# mediator.net
KiCad netlist of a schematic drawn in EAGLE
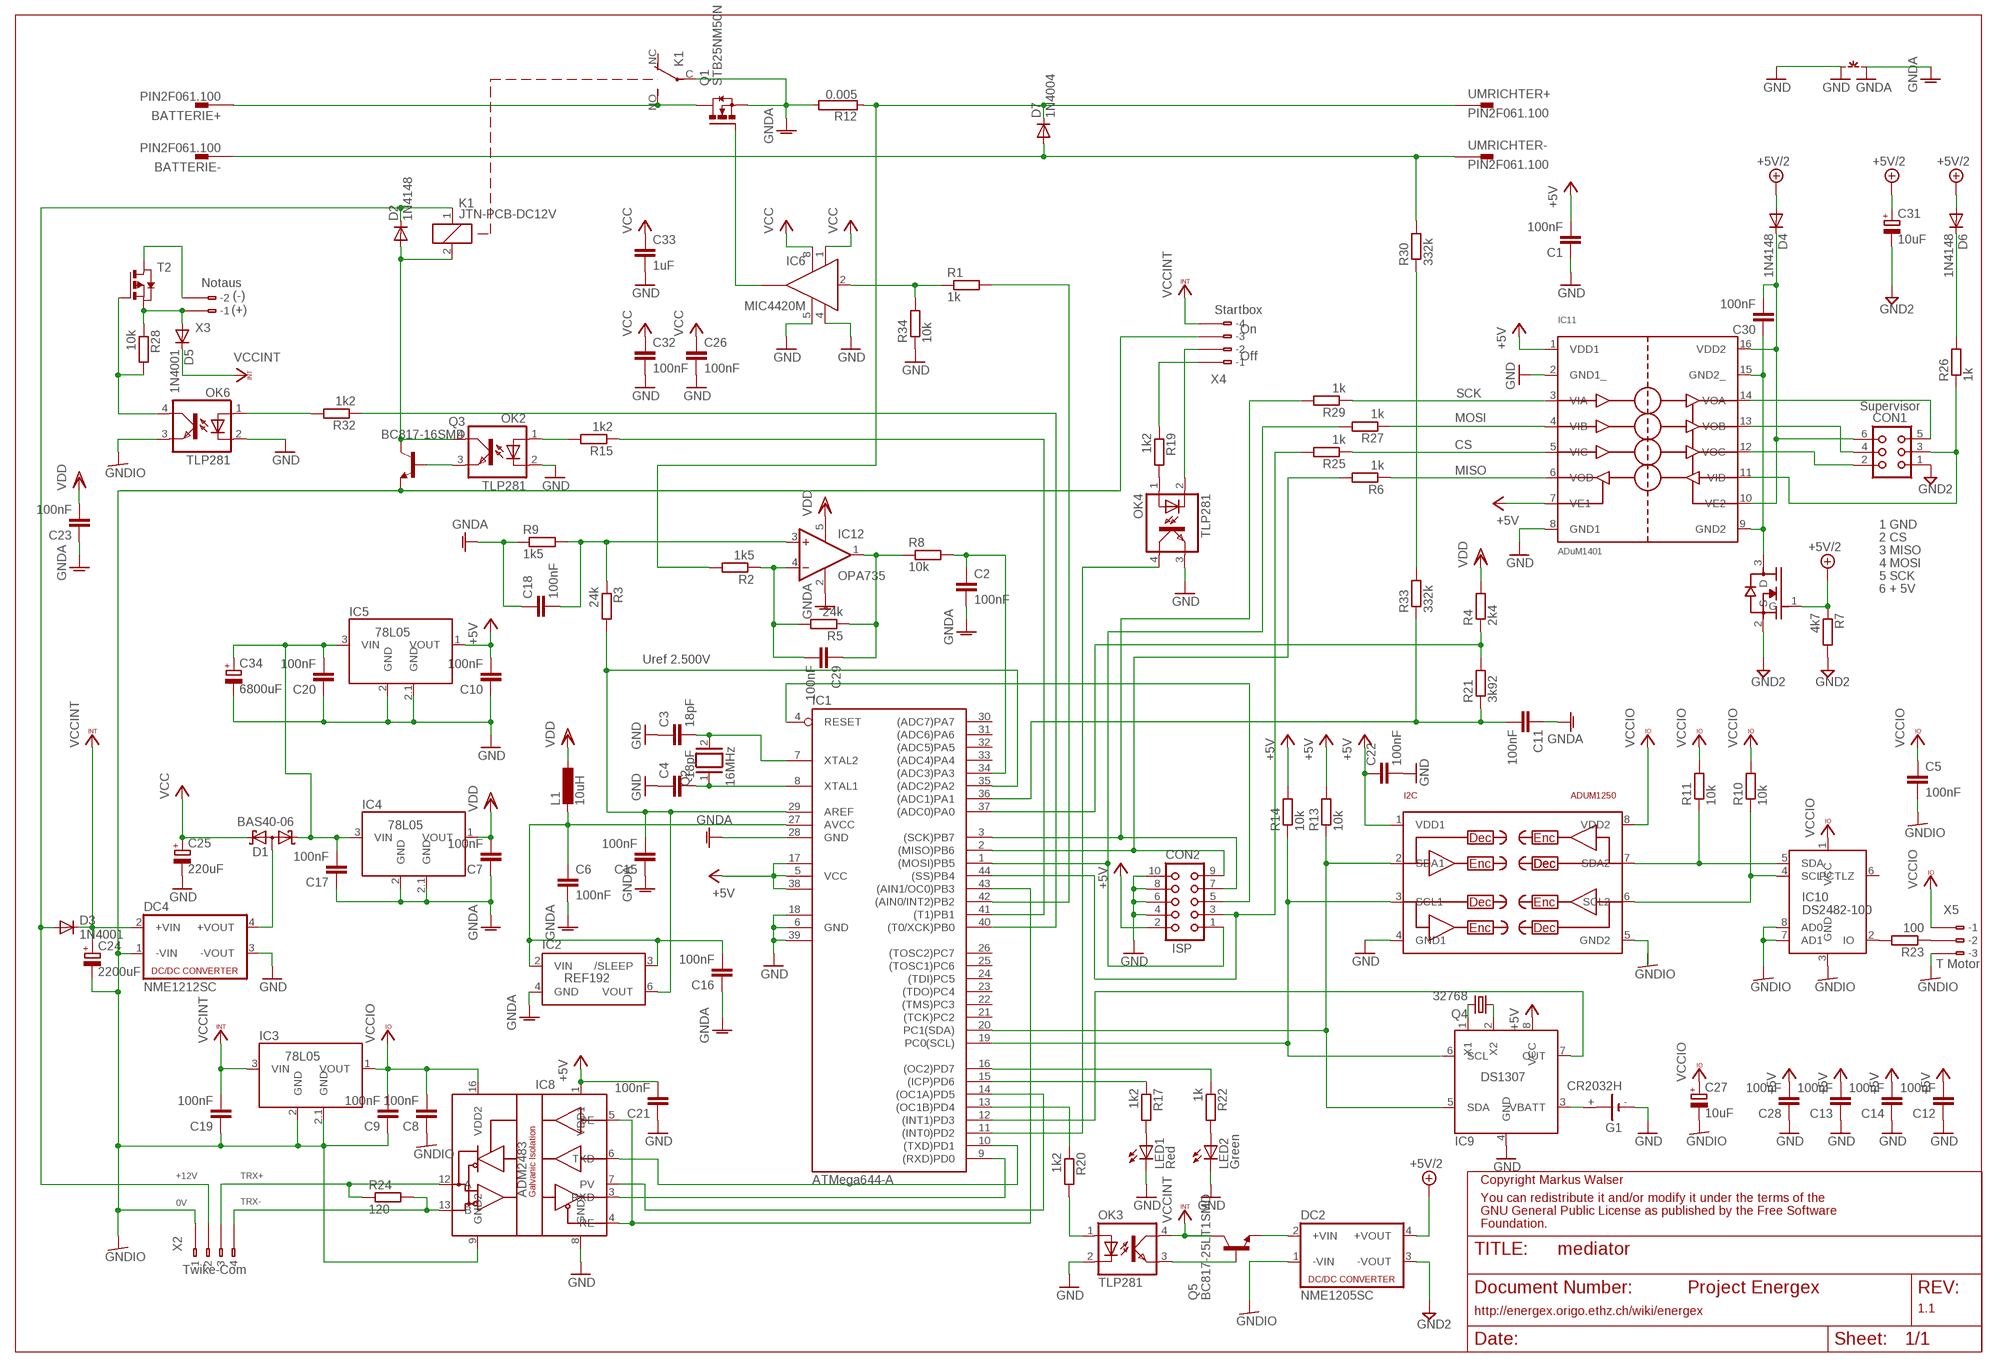
[diagram p0: schematic, sheet 1]

(export (version "E")
  (design (tool "Eeschema 10.0.6"))
  (components
    (comp (ref "BATTERIE+")
      (value "PIN2F061.100")
      (footprint "eagle-import:F061.100")
      (libsource (lib "eagle-import") (part "PIN2F061.100"))
    )
    (comp (ref "BATTERIE-")
      (value "PIN2F061.100")
      (footprint "eagle-import:F061.100")
      (libsource (lib "eagle-import") (part "PIN2F061.100"))
    )
    (comp (ref "C1")
      (value "100nF")
      (footprint "eagle-import:C0603K")
      (libsource (lib "eagle-import") (part "C-EUC0603K"))
    )
    (comp (ref "C2")
      (value "100nF")
      (footprint "eagle-import:C0603K")
      (libsource (lib "eagle-import") (part "C-EUC0603K"))
    )
    (comp (ref "C3")
      (value "18pF")
      (footprint "eagle-import:C0603K")
      (libsource (lib "eagle-import") (part "C-EUC0603K"))
    )
    (comp (ref "C4")
      (value "18pF")
      (footprint "eagle-import:C0603K")
      (libsource (lib "eagle-import") (part "C-EUC0603K"))
    )
    (comp (ref "C5")
      (value "100nF")
      (footprint "eagle-import:C0603K")
      (libsource (lib "eagle-import") (part "C-EUC0603K"))
    )
    (comp (ref "C6")
      (value "100nF")
      (footprint "eagle-import:C0603K")
      (libsource (lib "eagle-import") (part "C-EUC0603K"))
    )
    (comp (ref "C7")
      (value "100nF")
      (footprint "eagle-import:C0603K")
      (libsource (lib "eagle-import") (part "C-EUC0603K"))
    )
    (comp (ref "C8")
      (value "100nF")
      (footprint "eagle-import:C0603K")
      (libsource (lib "eagle-import") (part "C-EUC0603K"))
    )
    (comp (ref "C9")
      (value "100nF")
      (footprint "eagle-import:C0603K")
      (libsource (lib "eagle-import") (part "C-EUC0603K"))
    )
    (comp (ref "C10")
      (value "100nF")
      (footprint "eagle-import:C0603K")
      (libsource (lib "eagle-import") (part "C-EUC0603K"))
    )
    (comp (ref "C11")
      (value "100nF")
      (footprint "eagle-import:C0603K")
      (libsource (lib "eagle-import") (part "C-EUC0603K"))
    )
    (comp (ref "C12")
      (value "100nF")
      (footprint "eagle-import:C0603K")
      (libsource (lib "eagle-import") (part "C-EUC0603K"))
    )
    (comp (ref "C13")
      (value "100nF")
      (footprint "eagle-import:C0603K")
      (libsource (lib "eagle-import") (part "C-EUC0603K"))
    )
    (comp (ref "C14")
      (value "100nF")
      (footprint "eagle-import:C0603K")
      (libsource (lib "eagle-import") (part "C-EUC0603K"))
    )
    (comp (ref "C15")
      (value "100nF")
      (footprint "eagle-import:C0603K")
      (libsource (lib "eagle-import") (part "C-EUC0603K"))
    )
    (comp (ref "C16")
      (value "100nF")
      (footprint "eagle-import:C0603K")
      (libsource (lib "eagle-import") (part "C-EUC0603K"))
    )
    (comp (ref "C17")
      (value "100nF")
      (footprint "eagle-import:C0603K")
      (libsource (lib "eagle-import") (part "C-EUC0603K"))
    )
    (comp (ref "C18")
      (value "100nF")
      (footprint "eagle-import:C0603K")
      (libsource (lib "eagle-import") (part "C-EUC0603K"))
    )
    (comp (ref "C19")
      (value "100nF")
      (footprint "eagle-import:C0603K")
      (libsource (lib "eagle-import") (part "C-EUC0603K"))
    )
    (comp (ref "C20")
      (value "100nF")
      (footprint "eagle-import:C0603K")
      (libsource (lib "eagle-import") (part "C-EUC0603K"))
    )
    (comp (ref "C21")
      (value "100nF")
      (footprint "eagle-import:C0603K")
      (libsource (lib "eagle-import") (part "C-EUC0603K"))
    )
    (comp (ref "C22")
      (value "100nF")
      (footprint "eagle-import:C0603K")
      (libsource (lib "eagle-import") (part "C-EUC0603K"))
    )
    (comp (ref "C23")
      (value "100nF")
      (footprint "eagle-import:C0603K")
      (libsource (lib "eagle-import") (part "C-EUC0603K"))
    )
    (comp (ref "C24")
      (value "2200uF")
      (footprint "eagle-import:E5-10,5")
      (libsource (lib "eagle-import") (part "CPOL-EUE5-10.5"))
    )
    (comp (ref "C25")
      (value "220uF")
      (footprint "eagle-import:E2,5-6")
      (libsource (lib "eagle-import") (part "CPOL-EUE2.5-6"))
    )
    (comp (ref "C26")
      (value "100nF")
      (footprint "eagle-import:C0603K")
      (libsource (lib "eagle-import") (part "C-EUC0603K"))
    )
    (comp (ref "C27")
      (value "10uF")
      (footprint "eagle-import:SMC_A")
      (libsource (lib "eagle-import") (part "CPOL-EUSMCA"))
    )
    (comp (ref "C28")
      (value "100nF")
      (footprint "eagle-import:C0603K")
      (libsource (lib "eagle-import") (part "C-EUC0603K"))
    )
    (comp (ref "C29")
      (value "100nF")
      (footprint "eagle-import:C0603K")
      (libsource (lib "eagle-import") (part "C-EUC0603K"))
    )
    (comp (ref "C30")
      (value "100nF")
      (footprint "eagle-import:C0603K")
      (libsource (lib "eagle-import") (part "C-EUC0603K"))
    )
    (comp (ref "C31")
      (value "10uF")
      (footprint "eagle-import:SMC_A")
      (libsource (lib "eagle-import") (part "CPOL-EUSMCA"))
    )
    (comp (ref "C32")
      (value "100nF")
      (footprint "eagle-import:C0603K")
      (libsource (lib "eagle-import") (part "C-EUC0603K"))
    )
    (comp (ref "C33")
      (value "1uF")
      (footprint "eagle-import:C0603K")
      (libsource (lib "eagle-import") (part "C-EUC0603K"))
    )
    (comp (ref "C34")
      (value "6800uF")
      (footprint "eagle-import:E7,5-16")
      (libsource (lib "eagle-import") (part "CPOL-EUE7.5-16"))
    )
    (comp (ref "CON1")
      (value "CON06")
      (footprint "eagle-import:CON06")
      (libsource (lib "eagle-import") (part "CON06"))
    )
    (comp (ref "CON2")
      (value "CON10")
      (footprint "eagle-import:CON10")
      (libsource (lib "eagle-import") (part "CON10"))
    )
    (comp (ref "D1")
      (value "BAS40-06")
      (footprint "eagle-import:SOT23")
      (libsource (lib "eagle-import") (part "BAS40-06"))
    )
    (comp (ref "D2")
      (value "1N4148")
      (footprint "eagle-import:MICROMELF-R")
      (libsource (lib "eagle-import") (part "DIODE-MICROMELF-R"))
    )
    (comp (ref "D3")
      (value "1N4001")
      (footprint "eagle-import:DO214AC")
      (libsource (lib "eagle-import") (part "DIODE-DO214AC"))
    )
    (comp (ref "D4")
      (value "1N4148")
      (footprint "eagle-import:MICROMELF-R")
      (libsource (lib "eagle-import") (part "DIODE-MICROMELF-R"))
    )
    (comp (ref "D5")
      (value "1N4001")
      (footprint "eagle-import:DO214AC")
      (libsource (lib "eagle-import") (part "DIODE-DO214AC"))
    )
    (comp (ref "D6")
      (value "1N4148")
      (footprint "eagle-import:MICROMELF-R")
      (libsource (lib "eagle-import") (part "DIODE-MICROMELF-R"))
    )
    (comp (ref "D7")
      (value "1N4004")
      (footprint "eagle-import:DO41-10")
      (libsource (lib "eagle-import") (part "1N4004"))
    )
    (comp (ref "DC2")
      (value "NME1205SC")
      (footprint "eagle-import:NME")
      (fields (field (name "MF") "C & D TECHNOLOGIES, INC") (field (name "MPN") "NME1205D"))
      (libsource (lib "eagle-import") (part "NME"))
    )
    (comp (ref "DC4")
      (value "NME1212SC")
      (footprint "eagle-import:NME")
      (fields (field (name "MF") "C & D TECHNOLOGIES, INC") (field (name "MPN") "NME1205D"))
      (libsource (lib "eagle-import") (part "NME"))
    )
    (comp (ref "G1")
      (value "CR2032H")
      (footprint "eagle-import:CR2032H")
      (libsource (lib "eagle-import") (part "CR2032H"))
    )
    (comp (ref "I2C")
      (value "ADUM1250")
      (footprint "eagle-import:SO8")
      (libsource (lib "eagle-import") (part "ADUM1250"))
    )
    (comp (ref "IC1")
      (value "ATMega644-A")
      (footprint "eagle-import:TQFP44")
      (fields (field (name "MPN") "ATMEGA32-16AU"))
      (libsource (lib "eagle-import") (part "MEGA32-A"))
    )
    (comp (ref "IC2")
      (value "REF192")
      (footprint "eagle-import:SO08")
      (libsource (lib "eagle-import") (part "REF192"))
    )
    (comp (ref "IC3")
      (value "78L05")
      (footprint "eagle-import:SOT89")
      (libsource (lib "eagle-import") (part "78L05"))
    )
    (comp (ref "IC4")
      (value "78L05")
      (footprint "eagle-import:SOT89")
      (libsource (lib "eagle-import") (part "78L05"))
    )
    (comp (ref "IC5")
      (value "78L05")
      (footprint "eagle-import:SOT89")
      (libsource (lib "eagle-import") (part "78L05"))
    )
    (comp (ref "IC6")
      (value "MIC4420M")
      (footprint "eagle-import:SO-08")
      (libsource (lib "eagle-import") (part "MIC4420M"))
    )
    (comp (ref "IC8")
      (value "ADM2483")
      (footprint "eagle-import:SO16W")
      (libsource (lib "eagle-import") (part "ADM2483"))
    )
    (comp (ref "IC9")
      (value "DS1307")
      (footprint "eagle-import:SO08")
      (libsource (lib "eagle-import") (part "DS1307"))
    )
    (comp (ref "IC10")
      (value "DS2482-100")
      (footprint "eagle-import:SO08")
      (libsource (lib "eagle-import") (part "DS2482-100"))
    )
    (comp (ref "IC11")
      (value "ADuM1401")
      (footprint "eagle-import:SO16W")
      (libsource (lib "eagle-import") (part "ADUM1401"))
    )
    (comp (ref "IC12")
      (value "OPA735")
      (footprint "eagle-import:SOT23-5")
      (libsource (lib "eagle-import") (part "OPA743"))
    )
    (comp (ref "K1")
      (value "JTN-PCB-DC12V")
      (footprint "eagle-import:JT-PCB")
      (libsource (lib "eagle-import") (part "JT?-N-PCBDC12V"))
    )
    (comp (ref "L1")
      (value "10uH")
      (footprint "eagle-import:L3225M")
      (libsource (lib "eagle-import") (part "L-EUL3225M"))
    )
    (comp (ref "LED1")
      (value "Red")
      (footprint "eagle-import:CHIPLED_0805")
      (libsource (lib "eagle-import") (part "LEDCHIPLED_0805"))
    )
    (comp (ref "LED2")
      (value "Green")
      (footprint "eagle-import:CHIPLED_0805")
      (libsource (lib "eagle-import") (part "LEDCHIPLED_0805"))
    )
    (comp (ref "OK2")
      (value "TLP281")
      (footprint "eagle-import:MINI-FLAT-4")
      (libsource (lib "eagle-import") (part "TLP283"))
    )
    (comp (ref "OK3")
      (value "TLP281")
      (footprint "eagle-import:MINI-FLAT-4")
      (libsource (lib "eagle-import") (part "TLP283"))
    )
    (comp (ref "OK4")
      (value "TLP281")
      (footprint "eagle-import:MINI-FLAT-4")
      (libsource (lib "eagle-import") (part "TLP283"))
    )
    (comp (ref "OK6")
      (value "TLP281")
      (footprint "eagle-import:MINI-FLAT-4")
      (libsource (lib "eagle-import") (part "TLP283"))
    )
    (comp (ref "Q1")
      (value "STB25NM50N")
      (footprint "eagle-import:D2PACK")
      (libsource (lib "eagle-import") (part "IRF3704S"))
    )
    (comp (ref "Q2")
      (value "16MHz")
      (footprint "eagle-import:QS")
      (libsource (lib "eagle-import") (part "XTAL/S"))
    )
    (comp (ref "Q3")
      (value "BC817-16SMD")
      (footprint "eagle-import:SOT23-BEC")
      (libsource (lib "eagle-import") (part "BC817SMD-16"))
    )
    (comp (ref "Q4")
      (value "32768")
      (footprint "eagle-import:TC26H")
      (libsource (lib "eagle-import") (part "CRYSTALTC26H"))
    )
    (comp (ref "Q5")
      (value "BC817-25LT1SMD")
      (footprint "eagle-import:SOT23-BEC")
      (libsource (lib "eagle-import") (part "BC817SMD-25LT1"))
    )
    (comp (ref "R1")
      (value "1k")
      (footprint "eagle-import:R0603")
      (libsource (lib "eagle-import") (part "R-EU_R0603"))
    )
    (comp (ref "R2")
      (value "1k5")
      (footprint "eagle-import:M0805")
      (libsource (lib "eagle-import") (part "R-EU_M0805"))
    )
    (comp (ref "R3")
      (value "24k")
      (footprint "eagle-import:M0805")
      (libsource (lib "eagle-import") (part "R-EU_M0805"))
    )
    (comp (ref "R4")
      (value "2k4")
      (footprint "eagle-import:M0805")
      (libsource (lib "eagle-import") (part "R-EU_M0805"))
    )
    (comp (ref "R5")
      (value "24k")
      (footprint "eagle-import:M0805")
      (libsource (lib "eagle-import") (part "R-EU_M0805"))
    )
    (comp (ref "R6")
      (value "1k")
      (footprint "eagle-import:M0805")
      (libsource (lib "eagle-import") (part "R-EU_M0805"))
    )
    (comp (ref "R7")
      (value "4k7")
      (footprint "eagle-import:R0603")
      (libsource (lib "eagle-import") (part "R-EU_R0603"))
    )
    (comp (ref "R8")
      (value "10k")
      (footprint "eagle-import:M0805")
      (libsource (lib "eagle-import") (part "R-EU_M0805"))
    )
    (comp (ref "R9")
      (value "1k5")
      (footprint "eagle-import:M0805")
      (libsource (lib "eagle-import") (part "R-EU_M0805"))
    )
    (comp (ref "R10")
      (value "10k")
      (footprint "eagle-import:M0805")
      (libsource (lib "eagle-import") (part "R-EU_M0805"))
    )
    (comp (ref "R11")
      (value "10k")
      (footprint "eagle-import:M0805")
      (libsource (lib "eagle-import") (part "R-EU_M0805"))
    )
    (comp (ref "R12")
      (value "0.005")
      (footprint "eagle-import:KH208-8")
      (libsource (lib "eagle-import") (part "RKH208-8"))
    )
    (comp (ref "R13")
      (value "10k")
      (footprint "eagle-import:M0805")
      (libsource (lib "eagle-import") (part "R-EU_M0805"))
    )
    (comp (ref "R14")
      (value "10k")
      (footprint "eagle-import:M0805")
      (libsource (lib "eagle-import") (part "R-EU_M0805"))
    )
    (comp (ref "R15")
      (value "1k2")
      (footprint "eagle-import:R0603")
      (libsource (lib "eagle-import") (part "R-EU_R0603"))
    )
    (comp (ref "R17")
      (value "1k2")
      (footprint "eagle-import:R0603")
      (libsource (lib "eagle-import") (part "R-EU_R0603"))
    )
    (comp (ref "R19")
      (value "1k2")
      (footprint "eagle-import:R0603")
      (libsource (lib "eagle-import") (part "R-EU_R0603"))
    )
    (comp (ref "R20")
      (value "1k2")
      (footprint "eagle-import:R0603")
      (libsource (lib "eagle-import") (part "R-EU_R0603"))
    )
    (comp (ref "R21")
      (value "3k92")
      (footprint "eagle-import:M0805")
      (libsource (lib "eagle-import") (part "R-EU_M0805"))
    )
    (comp (ref "R22")
      (value "1k")
      (footprint "eagle-import:R0603")
      (libsource (lib "eagle-import") (part "R-EU_R0603"))
    )
    (comp (ref "R23")
      (value "100")
      (footprint "eagle-import:M0805")
      (libsource (lib "eagle-import") (part "R-EU_M0805"))
    )
    (comp (ref "R24")
      (value "120")
      (footprint "eagle-import:R0603")
      (libsource (lib "eagle-import") (part "R-EU_R0603"))
    )
    (comp (ref "R25")
      (value "1k")
      (footprint "eagle-import:M0805")
      (libsource (lib "eagle-import") (part "R-EU_M0805"))
    )
    (comp (ref "R26")
      (value "1k")
      (footprint "eagle-import:R0603")
      (libsource (lib "eagle-import") (part "R-EU_R0603"))
    )
    (comp (ref "R27")
      (value "1k")
      (footprint "eagle-import:M0805")
      (libsource (lib "eagle-import") (part "R-EU_M0805"))
    )
    (comp (ref "R28")
      (value "10k")
      (footprint "eagle-import:M0805")
      (libsource (lib "eagle-import") (part "R-EU_M0805"))
    )
    (comp (ref "R29")
      (value "1k")
      (footprint "eagle-import:M0805")
      (libsource (lib "eagle-import") (part "R-EU_M0805"))
    )
    (comp (ref "R30")
      (value "332k")
      (footprint "eagle-import:0207_10")
      (libsource (lib "eagle-import") (part "R-EU_0207/10"))
    )
    (comp (ref "R32")
      (value "1k2")
      (footprint "eagle-import:R0603")
      (libsource (lib "eagle-import") (part "R-EU_R0603"))
    )
    (comp (ref "R33")
      (value "332k")
      (footprint "eagle-import:0207_5V")
      (libsource (lib "eagle-import") (part "R-EU_0207/5V"))
    )
    (comp (ref "R34")
      (value "10k")
      (footprint "eagle-import:R0603")
      (libsource (lib "eagle-import") (part "R-EU_R0603"))
    )
    (comp (ref "T1")
      (value "FDN337N")
      (footprint "eagle-import:SOT23")
      (libsource (lib "eagle-import") (part "FDN337N"))
    )
    (comp (ref "T2")
      (value "PMOSSOT23")
      (footprint "eagle-import:SOT-23")
      (libsource (lib "eagle-import") (part "PMOSSOT23"))
    )
    (comp (ref "UMRICHTER+")
      (value "PIN2F061.100")
      (footprint "eagle-import:F061.100")
      (libsource (lib "eagle-import") (part "PIN2F061.100"))
    )
    (comp (ref "UMRICHTER-")
      (value "PIN2F061.100")
      (footprint "eagle-import:F061.100")
      (libsource (lib "eagle-import") (part "PIN2F061.100"))
    )
    (comp (ref "X2")
      (value "233-104")
      (footprint "eagle-import:233-104")
      (libsource (lib "eagle-import") (part "233-104"))
    )
    (comp (ref "X3")
      (value "233-102")
      (footprint "eagle-import:233-102")
      (libsource (lib "eagle-import") (part "233-102"))
    )
    (comp (ref "X4")
      (value "233-104")
      (footprint "eagle-import:233-104")
      (libsource (lib "eagle-import") (part "233-104"))
    )
    (comp (ref "X5")
      (value "233-203")
      (footprint "eagle-import:233-203")
      (libsource (lib "eagle-import") (part "233-203"))
    )
    (comp (ref "~NUDEV~1")
      (value "GND-GNDA")
      (footprint "eagle-import:GND-GNDA")
      (libsource (lib "eagle-import") (part "GND-GNDA"))
    )
  )
  (nets
    (net (code "1") (name "+5V") (class "Default")
      (node (ref "C1") (pin "2") (pinfunction "2_2") (pintype "passive"))
      (node (ref "C10") (pin "2") (pinfunction "2_2") (pintype "passive"))
      (node (ref "C12") (pin "2") (pinfunction "2_2") (pintype "passive"))
      (node (ref "C13") (pin "2") (pinfunction "2_2") (pintype "passive"))
      (node (ref "C14") (pin "2") (pinfunction "2_2") (pintype "passive"))
      (node (ref "C21") (pin "2") (pinfunction "2_2") (pintype "passive"))
      (node (ref "C22") (pin "1") (pinfunction "1_1") (pintype "passive"))
      (node (ref "C28") (pin "2") (pinfunction "2_2") (pintype "passive"))
      (node (ref "CON2") (pin "2") (pinfunction "2_2") (pintype "passive"))
      (node (ref "I2C") (pin "1") (pinfunction "VDD1_1") (pintype "power_in"))
      (node (ref "IC1") (pin "17") (pinfunction "VCC1_17") (pintype "power_in"))
      (node (ref "IC1") (pin "38") (pinfunction "VCC2_38") (pintype "power_in"))
      (node (ref "IC1") (pin "5") (pinfunction "VCC_5") (pintype "power_in"))
      (node (ref "IC11") (pin "1") (pinfunction "VDD1_1") (pintype "power_in"))
      (node (ref "IC11") (pin "7") (pinfunction "VE1_7") (pintype "input"))
      (node (ref "IC5") (pin "1") (pinfunction "VOUT_1") (pintype "power_in"))
      (node (ref "IC8") (pin "1") (pinfunction "VDD1_1") (pintype "power_in"))
      (node (ref "IC9") (pin "8") (pinfunction "VCC_8") (pintype "power_in"))
      (node (ref "R13") (pin "2") (pinfunction "2_2") (pintype "passive"))
      (node (ref "R14") (pin "2") (pinfunction "2_2") (pintype "passive"))
    )
    (net (code "2") (name "+5V{slash}2") (class "Default")
      (node (ref "C31") (pin "+") (pinfunction "+_+") (pintype "passive"))
      (node (ref "D4") (pin "A") (pinfunction "A_A") (pintype "passive"))
      (node (ref "D6") (pin "A") (pinfunction "A_A") (pintype "passive"))
      (node (ref "DC2") (pin "4") (pinfunction "+VOUT_4") (pintype "passive"))
      (node (ref "R7") (pin "1") (pinfunction "1_1") (pintype "passive"))
      (node (ref "T1") (pin "1") (pinfunction "G_1") (pintype "bidirectional"))
    )
    (net (code "3") (name "GND") (class "Default")
      (node (ref "C1") (pin "1") (pinfunction "1_1") (pintype "passive"))
      (node (ref "C10") (pin "1") (pinfunction "1_1") (pintype "passive"))
      (node (ref "C12") (pin "1") (pinfunction "1_1") (pintype "passive"))
      (node (ref "C13") (pin "1") (pinfunction "1_1") (pintype "passive"))
      (node (ref "C14") (pin "1") (pinfunction "1_1") (pintype "passive"))
      (node (ref "C20") (pin "1") (pinfunction "1_1") (pintype "passive"))
      (node (ref "C21") (pin "1") (pinfunction "1_1") (pintype "passive"))
      (node (ref "C22") (pin "2") (pinfunction "2_2") (pintype "passive"))
      (node (ref "C25") (pin "-") (pinfunction "-_-") (pintype "passive"))
      (node (ref "C26") (pin "2") (pinfunction "2_2") (pintype "passive"))
      (node (ref "C28") (pin "1") (pinfunction "1_1") (pintype "passive"))
      (node (ref "C3") (pin "1") (pinfunction "1_1") (pintype "passive"))
      (node (ref "C32") (pin "2") (pinfunction "2_2") (pintype "passive"))
      (node (ref "C33") (pin "2") (pinfunction "2_2") (pintype "passive"))
      (node (ref "C34") (pin "-") (pinfunction "-_-") (pintype "passive"))
      (node (ref "C4") (pin "1") (pinfunction "1_1") (pintype "passive"))
      (node (ref "CON2") (pin "10") (pinfunction "10_10") (pintype "passive"))
      (node (ref "CON2") (pin "4") (pinfunction "4_4") (pintype "passive"))
      (node (ref "CON2") (pin "6") (pinfunction "6_6") (pintype "passive"))
      (node (ref "CON2") (pin "8") (pinfunction "8_8") (pintype "passive"))
      (node (ref "DC4") (pin "3") (pinfunction "-VOUT_3") (pintype "passive"))
      (node (ref "G1") (pin "-") (pinfunction "-_-") (pintype "passive"))
      (node (ref "I2C") (pin "4") (pinfunction "GND1_4") (pintype "power_in"))
      (node (ref "IC1") (pin "18") (pinfunction "GND1_18") (pintype "power_in"))
      (node (ref "IC1") (pin "39") (pinfunction "GND2_39") (pintype "power_in"))
      (node (ref "IC1") (pin "6") (pinfunction "GND_6") (pintype "power_in"))
      (node (ref "IC11") (pin "2") (pinfunction "GND1__2") (pintype "power_in"))
      (node (ref "IC11") (pin "8") (pinfunction "GND1_8") (pintype "power_in"))
      (node (ref "IC5") (pin "2") (pinfunction "GND_2") (pintype "power_in"))
      (node (ref "IC5") (pin "2.1") (pinfunction "GND_2.1") (pintype "power_in"))
      (node (ref "IC6") (pin "4") (pinfunction "GND_4") (pintype "power_in"))
      (node (ref "IC6") (pin "5") (pinfunction "GND1_5") (pintype "power_in"))
      (node (ref "IC8") (pin "8") (pinfunction "GND1_8") (pintype "power_in"))
      (node (ref "IC9") (pin "4") (pinfunction "GND_4") (pintype "power_in"))
      (node (ref "LED1") (pin "C") (pinfunction "C_C") (pintype "passive"))
      (node (ref "LED2") (pin "C") (pinfunction "C_C") (pintype "passive"))
      (node (ref "OK2") (pin "2") (pinfunction "C_2") (pintype "passive"))
      (node (ref "OK3") (pin "2") (pinfunction "C_2") (pintype "passive"))
      (node (ref "OK4") (pin "3") (pinfunction "EMIT_3") (pintype "passive"))
      (node (ref "OK6") (pin "2") (pinfunction "C_2") (pintype "passive"))
      (node (ref "R34") (pin "1") (pinfunction "1_1") (pintype "passive"))
      (node (ref "~NUDEV~1") (pin "GND") (pinfunction "GND_GND") (pintype "power_in"))
    )
    (net (code "4") (name "GND2") (class "Default")
      (node (ref "C31") (pin "-") (pinfunction "-_-") (pintype "passive"))
      (node (ref "CON1") (pin "1") (pinfunction "1_1") (pintype "passive"))
      (node (ref "DC2") (pin "3") (pinfunction "-VOUT_3") (pintype "passive"))
      (node (ref "R7") (pin "2") (pinfunction "2_2") (pintype "passive"))
      (node (ref "T1") (pin "2") (pinfunction "S_2") (pintype "bidirectional"))
    )
    (net (code "5") (name "GNDA") (class "Default")
      (node (ref "C11") (pin "1") (pinfunction "1_1") (pintype "passive"))
      (node (ref "C15") (pin "1") (pinfunction "1_1") (pintype "passive"))
      (node (ref "C16") (pin "1") (pinfunction "1_1") (pintype "passive"))
      (node (ref "C17") (pin "1") (pinfunction "1_1") (pintype "passive"))
      (node (ref "C18") (pin "1") (pinfunction "1_1") (pintype "passive"))
      (node (ref "C2") (pin "2") (pinfunction "2_2") (pintype "passive"))
      (node (ref "C23") (pin "1") (pinfunction "1_1") (pintype "passive"))
      (node (ref "C6") (pin "2") (pinfunction "2_2") (pintype "passive"))
      (node (ref "C7") (pin "1") (pinfunction "1_1") (pintype "passive"))
      (node (ref "IC1") (pin "28") (pinfunction "GND_28") (pintype "power_in"))
      (node (ref "IC12") (pin "2") (pinfunction "V-_2") (pintype "power_in"))
      (node (ref "IC2") (pin "4") (pinfunction "GND_4") (pintype "bidirectional"))
      (node (ref "IC4") (pin "2") (pinfunction "GND_2") (pintype "power_in"))
      (node (ref "IC4") (pin "2.1") (pinfunction "GND_2.1") (pintype "power_in"))
      (node (ref "K1") (pin "C") (pinfunction "P_C") (pintype "passive"))
      (node (ref "Q1") (pin "3") (pinfunction "S_3") (pintype "passive"))
      (node (ref "R12") (pin "2") (pinfunction "2_2") (pintype "passive"))
      (node (ref "R9") (pin "1") (pinfunction "1_1") (pintype "passive"))
      (node (ref "~NUDEV~1") (pin "GNDA") (pinfunction "GNDA_GNDA") (pintype "power_in"))
    )
    (net (code "6") (name "GNDIO") (class "Default")
      (node (ref "C19") (pin "1") (pinfunction "1_1") (pintype "passive"))
      (node (ref "C24") (pin "-") (pinfunction "-_-") (pintype "passive"))
      (node (ref "C27") (pin "-") (pinfunction "-_-") (pintype "passive"))
      (node (ref "C5") (pin "2") (pinfunction "2_2") (pintype "passive"))
      (node (ref "C8") (pin "1") (pinfunction "1_1") (pintype "passive"))
      (node (ref "C9") (pin "1") (pinfunction "1_1") (pintype "passive"))
      (node (ref "DC2") (pin "1") (pinfunction "-VIN_1") (pintype "passive"))
      (node (ref "DC4") (pin "1") (pinfunction "-VIN_1") (pintype "passive"))
      (node (ref "I2C") (pin "5") (pinfunction "GND2_5") (pintype "power_in"))
      (node (ref "IC10") (pin "3") (pinfunction "GND_3") (pintype "power_in"))
      (node (ref "IC10") (pin "7") (pinfunction "AD1_7") (pintype "input"))
      (node (ref "IC10") (pin "8") (pinfunction "AD0_8") (pintype "input"))
      (node (ref "IC3") (pin "2") (pinfunction "GND_2") (pintype "power_in"))
      (node (ref "IC3") (pin "2.1") (pinfunction "GND_2.1") (pintype "power_in"))
      (node (ref "IC8") (pin "9") (pinfunction "GND2_9") (pintype "power_in"))
      (node (ref "OK6") (pin "3") (pinfunction "EMIT_3") (pintype "passive"))
      (node (ref "Q3") (pin "E") (pinfunction "E_E") (pintype "passive"))
      (node (ref "X2") (pin "B1") (pinfunction "B-1_B1") (pintype "passive"))
      (node (ref "X4") (pin "B3") (pinfunction "B-3_B3") (pintype "passive"))
      (node (ref "X5") (pin "B3") (pinfunction "B-3_B3") (pintype "passive"))
    )
    (net (code "7") (name "Net-(BATTERIE+-1)") (class "Default")
      (node (ref "BATTERIE+") (pin "A1") (pinfunction "1_A1") (pintype "passive"))
      (node (ref "K1") (pin "NO") (pinfunction "S_NO") (pintype "passive"))
      (node (ref "Q1") (pin "2") (pinfunction "D_2") (pintype "passive"))
    )
    (net (code "8") (name "Net-(BATTERIE--1)") (class "Default")
      (node (ref "BATTERIE-") (pin "A1") (pinfunction "1_A1") (pintype "passive"))
      (node (ref "D7") (pin "A") (pinfunction "A_A") (pintype "passive"))
      (node (ref "R30") (pin "2") (pinfunction "2_2") (pintype "passive"))
      (node (ref "UMRICHTER-") (pin "A1") (pinfunction "1_A1") (pintype "passive"))
    )
    (net (code "9") (name "Net-(D1-AA)") (class "Default")
      (node (ref "D1") (pin "3") (pinfunction "AA_3") (pintype "passive"))
      (node (ref "DC4") (pin "4") (pinfunction "+VOUT_4") (pintype "passive"))
    )
    (net (code "10") (name "Net-(D1-K1)") (class "Default")
      (node (ref "C17") (pin "2") (pinfunction "2_2") (pintype "passive"))
      (node (ref "C20") (pin "2") (pinfunction "2_2") (pintype "passive"))
      (node (ref "C34") (pin "+") (pinfunction "+_+") (pintype "passive"))
      (node (ref "D1") (pin "1") (pinfunction "K1_1") (pintype "passive"))
      (node (ref "IC4") (pin "3") (pinfunction "VIN_3") (pintype "power_in"))
      (node (ref "IC5") (pin "3") (pinfunction "VIN_3") (pintype "power_in"))
    )
    (net (code "11") (name "Net-(D6-PadC)") (class "Default")
      (node (ref "D6") (pin "C") (pinfunction "C_C") (pintype "passive"))
      (node (ref "R26") (pin "2") (pinfunction "2_2") (pintype "passive"))
    )
    (net (code "12") (name "Net-(DC2-+VIN)") (class "Default")
      (node (ref "DC2") (pin "2") (pinfunction "+VIN_2") (pintype "passive"))
      (node (ref "Q5") (pin "E") (pinfunction "E_E") (pintype "passive"))
    )
    (net (code "13") (name "Net-(I2C-SCL1)") (class "Default")
      (node (ref "I2C") (pin "3") (pinfunction "SCL1_3") (pintype "bidirectional"))
      (node (ref "IC1") (pin "19") (pinfunction "PC0(SCL)_19") (pintype "bidirectional"))
      (node (ref "IC9") (pin "6") (pinfunction "SCL_6") (pintype "bidirectional"))
      (node (ref "R14") (pin "1") (pinfunction "1_1") (pintype "passive"))
    )
    (net (code "14") (name "Net-(I2C-SCL2)") (class "Default")
      (node (ref "I2C") (pin "6") (pinfunction "SCL2_6") (pintype "bidirectional"))
      (node (ref "IC10") (pin "4") (pinfunction "SCL_4") (pintype "bidirectional"))
      (node (ref "R10") (pin "1") (pinfunction "1_1") (pintype "passive"))
    )
    (net (code "15") (name "Net-(I2C-SDA1)") (class "Default")
      (node (ref "I2C") (pin "2") (pinfunction "SDA1_2") (pintype "bidirectional"))
      (node (ref "IC1") (pin "20") (pinfunction "PC1(SDA)_20") (pintype "bidirectional"))
      (node (ref "IC9") (pin "5") (pinfunction "SDA_5") (pintype "bidirectional"))
      (node (ref "R13") (pin "1") (pinfunction "1_1") (pintype "passive"))
    )
    (net (code "16") (name "Net-(I2C-SDA2)") (class "Default")
      (node (ref "I2C") (pin "7") (pinfunction "SDA2_7") (pintype "bidirectional"))
      (node (ref "IC10") (pin "5") (pinfunction "SDA_5") (pintype "bidirectional"))
      (node (ref "R11") (pin "1") (pinfunction "1_1") (pintype "passive"))
    )
    (net (code "17") (name "Net-(IC1-(ADC0)PA0)") (class "Default")
      (node (ref "IC1") (pin "37") (pinfunction "(ADC0)PA0_37") (pintype "bidirectional"))
      (node (ref "R21") (pin "2") (pinfunction "2_2") (pintype "passive"))
      (node (ref "R4") (pin "1") (pinfunction "1_1") (pintype "passive"))
    )
    (net (code "18") (name "Net-(IC1-(ADC1)PA1)") (class "Default")
      (node (ref "C11") (pin "2") (pinfunction "2_2") (pintype "passive"))
      (node (ref "IC1") (pin "36") (pinfunction "(ADC1)PA1_36") (pintype "bidirectional"))
      (node (ref "R21") (pin "1") (pinfunction "1_1") (pintype "passive"))
      (node (ref "R33") (pin "1") (pinfunction "1_1") (pintype "passive"))
    )
    (net (code "19") (name "Net-(IC1-(ADC2)PA2)") (class "Default")
      (node (ref "C15") (pin "2") (pinfunction "2_2") (pintype "passive"))
      (node (ref "IC1") (pin "29") (pinfunction "AREF_29") (pintype "passive"))
      (node (ref "IC1") (pin "35") (pinfunction "(ADC2)PA2_35") (pintype "bidirectional"))
      (node (ref "IC2") (pin "6") (pinfunction "VOUT_6") (pintype "bidirectional"))
      (node (ref "R3") (pin "2") (pinfunction "2_2") (pintype "passive"))
    )
    (net (code "20") (name "Net-(IC1-(ADC3)PA3)") (class "Default")
      (node (ref "C2") (pin "1") (pinfunction "1_1") (pintype "passive"))
      (node (ref "IC1") (pin "34") (pinfunction "(ADC3)PA3_34") (pintype "bidirectional"))
      (node (ref "R8") (pin "2") (pinfunction "2_2") (pintype "passive"))
    )
    (net (code "21") (name "Net-(IC1-(AIN0{slash}INT2)PB2)") (class "Default")
      (node (ref "IC1") (pin "42") (pinfunction "(AIN0/INT2)PB2_42") (pintype "bidirectional"))
      (node (ref "R1") (pin "2") (pinfunction "2_2") (pintype "passive"))
    )
    (net (code "22") (name "Net-(IC1-(AIN1{slash}OC0)PB3)") (class "Default")
      (node (ref "IC1") (pin "43") (pinfunction "(AIN1/OC0)PB3_43") (pintype "bidirectional"))
      (node (ref "IC8") (pin "4") (pinfunction "RE_4") (pintype "input"))
      (node (ref "IC8") (pin "5") (pinfunction "DE_5") (pintype "input"))
    )
    (net (code "23") (name "Net-(IC1-(ICP)PD6)") (class "Default")
      (node (ref "IC1") (pin "15") (pinfunction "(ICP)PD6_15") (pintype "bidirectional"))
      (node (ref "R17") (pin "1") (pinfunction "1_1") (pintype "passive"))
    )
    (net (code "24") (name "Net-(IC1-(INT0)PD2)") (class "Default")
      (node (ref "IC1") (pin "11") (pinfunction "(INT0)PD2_11") (pintype "bidirectional"))
      (node (ref "OK4") (pin "4") (pinfunction "COL_4") (pintype "passive"))
    )
    (net (code "25") (name "Net-(IC1-(INT1)PD3)") (class "Default")
      (node (ref "IC1") (pin "12") (pinfunction "(INT1)PD3_12") (pintype "bidirectional"))
      (node (ref "IC9") (pin "7") (pinfunction "OUT_7") (pintype "output"))
    )
    (net (code "26") (name "Net-(IC1-(MISO)PB6)") (class "Default")
      (node (ref "CON2") (pin "9") (pinfunction "9_9") (pintype "passive"))
      (node (ref "IC1") (pin "2") (pinfunction "(MISO)PB6_2") (pintype "bidirectional"))
      (node (ref "R6") (pin "2") (pinfunction "2_2") (pintype "passive"))
    )
    (net (code "27") (name "Net-(IC1-(MOSI)PB5)") (class "Default")
      (node (ref "CON2") (pin "1") (pinfunction "1_1") (pintype "passive"))
      (node (ref "IC1") (pin "1") (pinfunction "(MOSI)PB5_1") (pintype "bidirectional"))
      (node (ref "R27") (pin "2") (pinfunction "2_2") (pintype "passive"))
    )
    (net (code "28") (name "Net-(IC1-(OC1A)PD5)") (class "Default")
      (node (ref "IC1") (pin "14") (pinfunction "(OC1A)PD5_14") (pintype "bidirectional"))
      (node (ref "IC8") (pin "7") (pinfunction "PV_7") (pintype "input"))
    )
    (net (code "29") (name "Net-(IC1-(OC1B)PD4)") (class "Default")
      (node (ref "IC1") (pin "13") (pinfunction "(OC1B)PD4_13") (pintype "bidirectional"))
      (node (ref "R20") (pin "1") (pinfunction "1_1") (pintype "passive"))
    )
    (net (code "30") (name "Net-(IC1-(OC2)PD7)") (class "Default")
      (node (ref "IC1") (pin "16") (pinfunction "(OC2)PD7_16") (pintype "bidirectional"))
      (node (ref "R22") (pin "1") (pinfunction "1_1") (pintype "passive"))
    )
    (net (code "31") (name "Net-(IC1-(RXD)PD0)") (class "Default")
      (node (ref "IC1") (pin "9") (pinfunction "(RXD)PD0_9") (pintype "bidirectional"))
      (node (ref "IC8") (pin "3") (pinfunction "RXD_3") (pintype "output"))
    )
    (net (code "32") (name "Net-(IC1-(SCK)PB7)") (class "Default")
      (node (ref "CON2") (pin "7") (pinfunction "7_7") (pintype "passive"))
      (node (ref "IC1") (pin "3") (pinfunction "(SCK)PB7_3") (pintype "bidirectional"))
      (node (ref "R29") (pin "2") (pinfunction "2_2") (pintype "passive"))
    )
    (net (code "33") (name "Net-(IC1-(SS)PB4)") (class "Default")
      (node (ref "CON2") (pin "3") (pinfunction "3_3") (pintype "passive"))
      (node (ref "IC1") (pin "44") (pinfunction "(SS)PB4_44") (pintype "bidirectional"))
      (node (ref "R25") (pin "2") (pinfunction "2_2") (pintype "passive"))
    )
    (net (code "34") (name "Net-(IC1-(T0{slash}XCK)PB0)") (class "Default")
      (node (ref "IC1") (pin "40") (pinfunction "(T0/XCK)PB0_40") (pintype "bidirectional"))
      (node (ref "R32") (pin "1") (pinfunction "1_1") (pintype "passive"))
    )
    (net (code "35") (name "Net-(IC1-(T1)PB1)") (class "Default")
      (node (ref "IC1") (pin "41") (pinfunction "(T1)PB1_41") (pintype "bidirectional"))
      (node (ref "R15") (pin "1") (pinfunction "1_1") (pintype "passive"))
    )
    (net (code "36") (name "Net-(IC1-(TXD)PD1)") (class "Default")
      (node (ref "IC1") (pin "10") (pinfunction "(TXD)PD1_10") (pintype "bidirectional"))
      (node (ref "IC8") (pin "6") (pinfunction "TXD_6") (pintype "input"))
    )
    (net (code "37") (name "Net-(IC1-AVCC)") (class "Default")
      (node (ref "C16") (pin "2") (pinfunction "2_2") (pintype "passive"))
      (node (ref "C6") (pin "1") (pinfunction "1_1") (pintype "passive"))
      (node (ref "IC1") (pin "27") (pinfunction "AVCC_27") (pintype "power_in"))
      (node (ref "IC2") (pin "2") (pinfunction "VIN_2") (pintype "bidirectional"))
      (node (ref "IC2") (pin "3") (pinfunction "/SLEEP_3") (pintype "bidirectional"))
      (node (ref "L1") (pin "2") (pinfunction "2_2") (pintype "passive"))
    )
    (net (code "38") (name "Net-(IC1-RESET)") (class "Default")
      (node (ref "CON2") (pin "5") (pinfunction "5_5") (pintype "passive"))
      (node (ref "IC1") (pin "4") (pinfunction "RESET_4") (pintype "input"))
    )
    (net (code "39") (name "Net-(IC1-XTAL1)") (class "Default")
      (node (ref "C4") (pin "2") (pinfunction "2_2") (pintype "passive"))
      (node (ref "IC1") (pin "8") (pinfunction "XTAL1_8") (pintype "bidirectional"))
      (node (ref "Q2") (pin "1") (pinfunction "1_1") (pintype "passive"))
    )
    (net (code "40") (name "Net-(IC1-XTAL2)") (class "Default")
      (node (ref "C3") (pin "2") (pinfunction "2_2") (pintype "passive"))
      (node (ref "IC1") (pin "7") (pinfunction "XTAL2_7") (pintype "bidirectional"))
      (node (ref "Q2") (pin "2") (pinfunction "2_2") (pintype "passive"))
    )
    (net (code "41") (name "Net-(IC6-IN)") (class "Default")
      (node (ref "IC6") (pin "2") (pinfunction "IN_2") (pintype "input"))
      (node (ref "R1") (pin "1") (pinfunction "1_1") (pintype "passive"))
      (node (ref "R34") (pin "2") (pinfunction "2_2") (pintype "passive"))
    )
    (net (code "42") (name "Net-(IC8-A)") (class "Default")
      (node (ref "IC8") (pin "12") (pinfunction "A_12") (pintype "bidirectional"))
      (node (ref "R24") (pin "1") (pinfunction "1_1") (pintype "passive"))
      (node (ref "X2") (pin "B3") (pinfunction "B-3_B3") (pintype "passive"))
    )
    (net (code "43") (name "Net-(IC8-B)") (class "Default")
      (node (ref "IC8") (pin "13") (pinfunction "B_13") (pintype "bidirectional"))
      (node (ref "R24") (pin "2") (pinfunction "2_2") (pintype "passive"))
      (node (ref "X2") (pin "B4") (pinfunction "B-4_B4") (pintype "passive"))
    )
    (net (code "44") (name "Net-(IC9-VBATT)") (class "Default")
      (node (ref "G1") (pin "+") (pinfunction "+_+") (pintype "passive"))
      (node (ref "IC9") (pin "3") (pinfunction "VBATT_3") (pintype "power_in"))
    )
    (net (code "45") (name "Net-(IC9-X1)") (class "Default")
      (node (ref "IC9") (pin "1") (pinfunction "X1_1") (pintype "bidirectional"))
      (node (ref "Q4") (pin "2") (pinfunction "2_2") (pintype "passive"))
    )
    (net (code "46") (name "Net-(IC9-X2)") (class "Default")
      (node (ref "IC9") (pin "2") (pinfunction "X2_2") (pintype "bidirectional"))
      (node (ref "Q4") (pin "1") (pinfunction "1_1") (pintype "passive"))
    )
    (net (code "47") (name "Net-(IC10-IO)") (class "Default")
      (node (ref "IC10") (pin "2") (pinfunction "IO_2") (pintype "bidirectional"))
      (node (ref "R23") (pin "2") (pinfunction "2_2") (pintype "passive"))
    )
    (net (code "48") (name "Net-(IC11-GND2)") (class "Default")
      (node (ref "C30") (pin "1") (pinfunction "1_1") (pintype "passive"))
      (node (ref "IC11") (pin "15") (pinfunction "GND2__15") (pintype "power_in"))
      (node (ref "IC11") (pin "9") (pinfunction "GND2_9") (pintype "power_in"))
      (node (ref "T1") (pin "3") (pinfunction "D_3") (pintype "bidirectional"))
    )
    (net (code "49") (name "Net-(IC11-VDD2)") (class "Default")
      (node (ref "C30") (pin "2") (pinfunction "2_2") (pintype "passive"))
      (node (ref "CON1") (pin "6") (pinfunction "6_6") (pintype "passive"))
      (node (ref "D4") (pin "C") (pinfunction "C_C") (pintype "passive"))
      (node (ref "IC11") (pin "10") (pinfunction "VE2_10") (pintype "input"))
      (node (ref "IC11") (pin "16") (pinfunction "VDD2_16") (pintype "power_in"))
    )
    (net (code "50") (name "Net-(IC11-VIA)") (class "Default")
      (node (ref "IC11") (pin "3") (pinfunction "VIA_3") (pintype "input"))
      (node (ref "R29") (pin "1") (pinfunction "1_1") (pintype "passive"))
    )
    (net (code "51") (name "Net-(IC11-VIB)") (class "Default")
      (node (ref "IC11") (pin "4") (pinfunction "VIB_4") (pintype "input"))
      (node (ref "R27") (pin "1") (pinfunction "1_1") (pintype "passive"))
    )
    (net (code "52") (name "Net-(IC11-VIC)") (class "Default")
      (node (ref "IC11") (pin "5") (pinfunction "VIC_5") (pintype "input"))
      (node (ref "R25") (pin "1") (pinfunction "1_1") (pintype "passive"))
    )
    (net (code "53") (name "Net-(IC11-VID)") (class "Default")
      (node (ref "CON1") (pin "3") (pinfunction "3_3") (pintype "passive"))
      (node (ref "IC11") (pin "11") (pinfunction "VID_11") (pintype "input"))
      (node (ref "R26") (pin "1") (pinfunction "1_1") (pintype "passive"))
    )
    (net (code "54") (name "Net-(IC11-VOA)") (class "Default")
      (node (ref "CON1") (pin "5") (pinfunction "5_5") (pintype "passive"))
      (node (ref "IC11") (pin "14") (pinfunction "VOA_14") (pintype "output"))
    )
    (net (code "55") (name "Net-(IC11-VOB)") (class "Default")
      (node (ref "CON1") (pin "4") (pinfunction "4_4") (pintype "passive"))
      (node (ref "IC11") (pin "13") (pinfunction "VOB_13") (pintype "output"))
    )
    (net (code "56") (name "Net-(IC11-VOC)") (class "Default")
      (node (ref "CON1") (pin "2") (pinfunction "2_2") (pintype "passive"))
      (node (ref "IC11") (pin "12") (pinfunction "VOC_12") (pintype "output"))
    )
    (net (code "57") (name "Net-(IC11-VOD)") (class "Default")
      (node (ref "IC11") (pin "6") (pinfunction "VOD_6") (pintype "output"))
      (node (ref "R6") (pin "1") (pinfunction "1_1") (pintype "passive"))
    )
    (net (code "58") (name "Net-(IC12-+IN)") (class "Default")
      (node (ref "C18") (pin "2") (pinfunction "2_2") (pintype "passive"))
      (node (ref "IC12") (pin "3") (pinfunction "+IN_3") (pintype "input"))
      (node (ref "R3") (pin "1") (pinfunction "1_1") (pintype "passive"))
      (node (ref "R9") (pin "2") (pinfunction "2_2") (pintype "passive"))
    )
    (net (code "59") (name "Net-(IC12--IN)") (class "Default")
      (node (ref "C29") (pin "2") (pinfunction "2_2") (pintype "passive"))
      (node (ref "IC12") (pin "4") (pinfunction "-IN_4") (pintype "input"))
      (node (ref "R2") (pin "1") (pinfunction "1_1") (pintype "passive"))
      (node (ref "R5") (pin "2") (pinfunction "2_2") (pintype "passive"))
    )
    (net (code "60") (name "Net-(IC12-OUT)") (class "Default")
      (node (ref "C29") (pin "1") (pinfunction "1_1") (pintype "passive"))
      (node (ref "IC12") (pin "1") (pinfunction "OUT_1") (pintype "output"))
      (node (ref "R5") (pin "1") (pinfunction "1_1") (pintype "passive"))
      (node (ref "R8") (pin "1") (pinfunction "1_1") (pintype "passive"))
    )
    (net (code "61") (name "Net-(LED1-PadA)") (class "Default")
      (node (ref "LED1") (pin "A") (pinfunction "A_A") (pintype "passive"))
      (node (ref "R17") (pin "2") (pinfunction "2_2") (pintype "passive"))
    )
    (net (code "62") (name "Net-(LED2-PadA)") (class "Default")
      (node (ref "LED2") (pin "A") (pinfunction "A_A") (pintype "passive"))
      (node (ref "R22") (pin "2") (pinfunction "2_2") (pintype "passive"))
    )
    (net (code "63") (name "Net-(OK2-A)") (class "Default")
      (node (ref "OK2") (pin "1") (pinfunction "A_1") (pintype "passive"))
      (node (ref "R15") (pin "2") (pinfunction "2_2") (pintype "passive"))
    )
    (net (code "64") (name "Net-(OK2-COL)") (class "Default")
      (node (ref "D2") (pin "A") (pinfunction "A_A") (pintype "passive"))
      (node (ref "K1") (pin "2") (pinfunction "2_2") (pintype "passive"))
      (node (ref "OK2") (pin "4") (pinfunction "COL_4") (pintype "passive"))
      (node (ref "Q3") (pin "C") (pinfunction "C_C") (pintype "passive"))
    )
    (net (code "65") (name "Net-(OK2-EMIT)") (class "Default")
      (node (ref "OK2") (pin "3") (pinfunction "EMIT_3") (pintype "passive"))
      (node (ref "Q3") (pin "B") (pinfunction "B_B") (pintype "passive"))
    )
    (net (code "66") (name "Net-(OK3-A)") (class "Default")
      (node (ref "OK3") (pin "1") (pinfunction "A_1") (pintype "passive"))
      (node (ref "R20") (pin "2") (pinfunction "2_2") (pintype "passive"))
    )
    (net (code "67") (name "Net-(OK3-EMIT)") (class "Default")
      (node (ref "OK3") (pin "3") (pinfunction "EMIT_3") (pintype "passive"))
      (node (ref "Q5") (pin "B") (pinfunction "B_B") (pintype "passive"))
    )
    (net (code "68") (name "Net-(OK4-A)") (class "Default")
      (node (ref "OK4") (pin "1") (pinfunction "A_1") (pintype "passive"))
      (node (ref "R19") (pin "2") (pinfunction "2_2") (pintype "passive"))
    )
    (net (code "69") (name "Net-(OK4-C)") (class "Default")
      (node (ref "OK4") (pin "2") (pinfunction "C_2") (pintype "passive"))
      (node (ref "X4") (pin "B2") (pinfunction "B-2_B2") (pintype "passive"))
    )
    (net (code "70") (name "Net-(OK6-A)") (class "Default")
      (node (ref "OK6") (pin "1") (pinfunction "A_1") (pintype "passive"))
      (node (ref "R32") (pin "2") (pinfunction "2_2") (pintype "passive"))
    )
    (net (code "71") (name "Net-(OK6-COL)") (class "Default")
      (node (ref "OK6") (pin "4") (pinfunction "COL_4") (pintype "passive"))
      (node (ref "R28") (pin "2") (pinfunction "2_2") (pintype "passive"))
      (node (ref "T2") (pin "3") (pinfunction "G_3") (pintype "passive"))
    )
    (net (code "72") (name "Net-(Q1-G)") (class "Default")
      (node (ref "IC6") (pin "6") (pinfunction "OUT_6") (pintype "passive"))
      (node (ref "Q1") (pin "1") (pinfunction "G_1") (pintype "passive"))
    )
    (net (code "73") (name "Net-(R30-Pad1)") (class "Default")
      (node (ref "R30") (pin "1") (pinfunction "1_1") (pintype "passive"))
      (node (ref "R33") (pin "2") (pinfunction "2_2") (pintype "passive"))
    )
    (net (code "74") (name "Net-(T2-D)") (class "Default")
      (node (ref "T2") (pin "1") (pinfunction "D_1") (pintype "passive"))
      (node (ref "X3") (pin "B2") (pinfunction "B-2_B2") (pintype "passive"))
    )
    (net (code "75") (name "Net-(T2-S)") (class "Default")
      (node (ref "D5") (pin "A") (pinfunction "A_A") (pintype "passive"))
      (node (ref "R28") (pin "1") (pinfunction "1_1") (pintype "passive"))
      (node (ref "T2") (pin "2") (pinfunction "S_2") (pintype "passive"))
      (node (ref "X3") (pin "B1") (pinfunction "B-1_B1") (pintype "passive"))
    )
    (net (code "76") (name "Net-(UMRICHTER+-1)") (class "Default")
      (node (ref "D7") (pin "C") (pinfunction "C_C") (pintype "passive"))
      (node (ref "R12") (pin "1") (pinfunction "1_1") (pintype "passive"))
      (node (ref "R2") (pin "2") (pinfunction "2_2") (pintype "passive"))
      (node (ref "UMRICHTER+") (pin "A1") (pinfunction "1_A1") (pintype "passive"))
    )
    (net (code "77") (name "Net-(X2-B-2)") (class "Default")
      (node (ref "D2") (pin "C") (pinfunction "C_C") (pintype "passive"))
      (node (ref "D3") (pin "A") (pinfunction "A_A") (pintype "passive"))
      (node (ref "K1") (pin "1") (pinfunction "1_1") (pintype "passive"))
      (node (ref "X2") (pin "B2") (pinfunction "B-2_B2") (pintype "passive"))
    )
    (net (code "78") (name "Net-(X4-B-1)") (class "Default")
      (node (ref "R19") (pin "1") (pinfunction "1_1") (pintype "passive"))
      (node (ref "X4") (pin "B1") (pinfunction "B-1_B1") (pintype "passive"))
    )
    (net (code "79") (name "Net-(X5-B-2)") (class "Default")
      (node (ref "R23") (pin "1") (pinfunction "1_1") (pintype "passive"))
      (node (ref "X5") (pin "B2") (pinfunction "B-2_B2") (pintype "passive"))
    )
    (net (code "80") (name "VCC") (class "Default")
      (node (ref "C25") (pin "+") (pinfunction "+_+") (pintype "passive"))
      (node (ref "C26") (pin "1") (pinfunction "1_1") (pintype "passive"))
      (node (ref "C32") (pin "1") (pinfunction "1_1") (pintype "passive"))
      (node (ref "C33") (pin "1") (pinfunction "1_1") (pintype "passive"))
      (node (ref "D1") (pin "2") (pinfunction "K2_2") (pintype "passive"))
      (node (ref "IC6") (pin "1") (pinfunction "VS_1") (pintype "power_in"))
      (node (ref "IC6") (pin "8") (pinfunction "VS1_8") (pintype "power_in"))
    )
    (net (code "81") (name "VCCINT") (class "Default")
      (node (ref "C19") (pin "2") (pinfunction "2_2") (pintype "passive"))
      (node (ref "C24") (pin "+") (pinfunction "+_+") (pintype "passive"))
      (node (ref "D3") (pin "C") (pinfunction "C_C") (pintype "passive"))
      (node (ref "D5") (pin "C") (pinfunction "C_C") (pintype "passive"))
      (node (ref "DC4") (pin "2") (pinfunction "+VIN_2") (pintype "passive"))
      (node (ref "IC3") (pin "3") (pinfunction "VIN_3") (pintype "power_in"))
      (node (ref "OK3") (pin "4") (pinfunction "COL_4") (pintype "passive"))
      (node (ref "Q5") (pin "C") (pinfunction "C_C") (pintype "passive"))
      (node (ref "X4") (pin "B4") (pinfunction "B-4_B4") (pintype "passive"))
    )
    (net (code "82") (name "VCCIO") (class "Default")
      (node (ref "C27") (pin "+") (pinfunction "+_+") (pintype "passive"))
      (node (ref "C5") (pin "1") (pinfunction "1_1") (pintype "passive"))
      (node (ref "C8") (pin "2") (pinfunction "2_2") (pintype "passive"))
      (node (ref "C9") (pin "2") (pinfunction "2_2") (pintype "passive"))
      (node (ref "I2C") (pin "8") (pinfunction "VDD2_8") (pintype "power_in"))
      (node (ref "IC10") (pin "1") (pinfunction "VCC_1") (pintype "power_in"))
      (node (ref "IC3") (pin "1") (pinfunction "VOUT_1") (pintype "power_in"))
      (node (ref "IC8") (pin "16") (pinfunction "VDD2_16") (pintype "power_in"))
      (node (ref "R10") (pin "2") (pinfunction "2_2") (pintype "passive"))
      (node (ref "R11") (pin "2") (pinfunction "2_2") (pintype "passive"))
      (node (ref "X5") (pin "B1") (pinfunction "B-1_B1") (pintype "passive"))
    )
    (net (code "83") (name "VDD") (class "Default")
      (node (ref "C23") (pin "2") (pinfunction "2_2") (pintype "passive"))
      (node (ref "C7") (pin "2") (pinfunction "2_2") (pintype "passive"))
      (node (ref "IC12") (pin "5") (pinfunction "V+_5") (pintype "power_in"))
      (node (ref "IC4") (pin "1") (pinfunction "VOUT_1") (pintype "power_in"))
      (node (ref "L1") (pin "1") (pinfunction "1_1") (pintype "passive"))
      (node (ref "R4") (pin "2") (pinfunction "2_2") (pintype "passive"))
    )
    (net (code "84") (name "unconnected-(BATTERIE+-1.1-PadA2)") (class "Default")
      (node (ref "BATTERIE+") (pin "A2") (pinfunction "1.1_A2") (pintype "passive"))
    )
    (net (code "85") (name "unconnected-(BATTERIE--1.1-PadA2)") (class "Default")
      (node (ref "BATTERIE-") (pin "A2") (pinfunction "1.1_A2") (pintype "passive"))
    )
    (net (code "86") (name "unconnected-(G1-+-Pad+@1)") (class "Default")
      (node (ref "G1") (pin "+@1") (pinfunction "+_+@1") (pintype "passive"))
    )
    (net (code "87") (name "unconnected-(IC1-(ADC4)PA4-Pad33)") (class "Default")
      (node (ref "IC1") (pin "33") (pinfunction "(ADC4)PA4_33") (pintype "bidirectional"))
    )
    (net (code "88") (name "unconnected-(IC1-(ADC5)PA5-Pad32)") (class "Default")
      (node (ref "IC1") (pin "32") (pinfunction "(ADC5)PA5_32") (pintype "bidirectional"))
    )
    (net (code "89") (name "unconnected-(IC1-(ADC6)PA6-Pad31)") (class "Default")
      (node (ref "IC1") (pin "31") (pinfunction "(ADC6)PA6_31") (pintype "bidirectional"))
    )
    (net (code "90") (name "unconnected-(IC1-(ADC7)PA7-Pad30)") (class "Default")
      (node (ref "IC1") (pin "30") (pinfunction "(ADC7)PA7_30") (pintype "bidirectional"))
    )
    (net (code "91") (name "unconnected-(IC1-(TCK)PC2-Pad21)") (class "Default")
      (node (ref "IC1") (pin "21") (pinfunction "(TCK)PC2_21") (pintype "bidirectional"))
    )
    (net (code "92") (name "unconnected-(IC1-(TDI)PC5-Pad24)") (class "Default")
      (node (ref "IC1") (pin "24") (pinfunction "(TDI)PC5_24") (pintype "bidirectional"))
    )
    (net (code "93") (name "unconnected-(IC1-(TDO)PC4-Pad23)") (class "Default")
      (node (ref "IC1") (pin "23") (pinfunction "(TDO)PC4_23") (pintype "bidirectional"))
    )
    (net (code "94") (name "unconnected-(IC1-(TMS)PC3-Pad22)") (class "Default")
      (node (ref "IC1") (pin "22") (pinfunction "(TMS)PC3_22") (pintype "bidirectional"))
    )
    (net (code "95") (name "unconnected-(IC1-(TOSC1)PC6-Pad25)") (class "Default")
      (node (ref "IC1") (pin "25") (pinfunction "(TOSC1)PC6_25") (pintype "bidirectional"))
    )
    (net (code "96") (name "unconnected-(IC1-(TOSC2)PC7-Pad26)") (class "Default")
      (node (ref "IC1") (pin "26") (pinfunction "(TOSC2)PC7_26") (pintype "bidirectional"))
    )
    (net (code "97") (name "unconnected-(IC6-OUT-Pad7)") (class "Default")
      (node (ref "IC6") (pin "7") (pinfunction "OUT_7") (pintype "passive"))
    )
    (net (code "98") (name "unconnected-(IC10-PCTLZ-Pad6)") (class "Default")
      (node (ref "IC10") (pin "6") (pinfunction "PCTLZ_6") (pintype "output"))
    )
    (net (code "99") (name "unconnected-(K1B-O-PadNC)") (class "Default")
      (node (ref "K1") (pin "NC") (pinfunction "O_NC") (pintype "passive"))
    )
    (net (code "100") (name "unconnected-(UMRICHTER+-1.1-PadA2)") (class "Default")
      (node (ref "UMRICHTER+") (pin "A2") (pinfunction "1.1_A2") (pintype "passive"))
    )
    (net (code "101") (name "unconnected-(UMRICHTER--1.1-PadA2)") (class "Default")
      (node (ref "UMRICHTER-") (pin "A2") (pinfunction "1.1_A2") (pintype "passive"))
    )
    (net (code "102") (name "unconnected-(X2--1-PadA1)") (class "Default")
      (node (ref "X2") (pin "A1") (pinfunction "-1_A1") (pintype "passive"))
    )
    (net (code "103") (name "unconnected-(X2--2-PadA2)") (class "Default")
      (node (ref "X2") (pin "A2") (pinfunction "-2_A2") (pintype "passive"))
    )
    (net (code "104") (name "unconnected-(X2--3-PadA3)") (class "Default")
      (node (ref "X2") (pin "A3") (pinfunction "-3_A3") (pintype "passive"))
    )
    (net (code "105") (name "unconnected-(X2--4-PadA4)") (class "Default")
      (node (ref "X2") (pin "A4") (pinfunction "-4_A4") (pintype "passive"))
    )
    (net (code "106") (name "unconnected-(X3--1-PadA1)") (class "Default")
      (node (ref "X3") (pin "A1") (pinfunction "-1_A1") (pintype "passive"))
    )
    (net (code "107") (name "unconnected-(X3--2-PadA2)") (class "Default")
      (node (ref "X3") (pin "A2") (pinfunction "-2_A2") (pintype "passive"))
    )
    (net (code "108") (name "unconnected-(X4--1-PadA1)") (class "Default")
      (node (ref "X4") (pin "A1") (pinfunction "-1_A1") (pintype "passive"))
    )
    (net (code "109") (name "unconnected-(X4--2-PadA2)") (class "Default")
      (node (ref "X4") (pin "A2") (pinfunction "-2_A2") (pintype "passive"))
    )
    (net (code "110") (name "unconnected-(X4--3-PadA3)") (class "Default")
      (node (ref "X4") (pin "A3") (pinfunction "-3_A3") (pintype "passive"))
    )
    (net (code "111") (name "unconnected-(X4--4-PadA4)") (class "Default")
      (node (ref "X4") (pin "A4") (pinfunction "-4_A4") (pintype "passive"))
    )
    (net (code "112") (name "unconnected-(X5--1-PadA1)") (class "Default")
      (node (ref "X5") (pin "A1") (pinfunction "-1_A1") (pintype "passive"))
    )
    (net (code "113") (name "unconnected-(X5--2-PadA2)") (class "Default")
      (node (ref "X5") (pin "A2") (pinfunction "-2_A2") (pintype "passive"))
    )
    (net (code "114") (name "unconnected-(X5--3-PadA3)") (class "Default")
      (node (ref "X5") (pin "A3") (pinfunction "-3_A3") (pintype "passive"))
    )
  )
)
